# ch340_usb.net
KiCad netlist of a schematic drawn in EAGLE
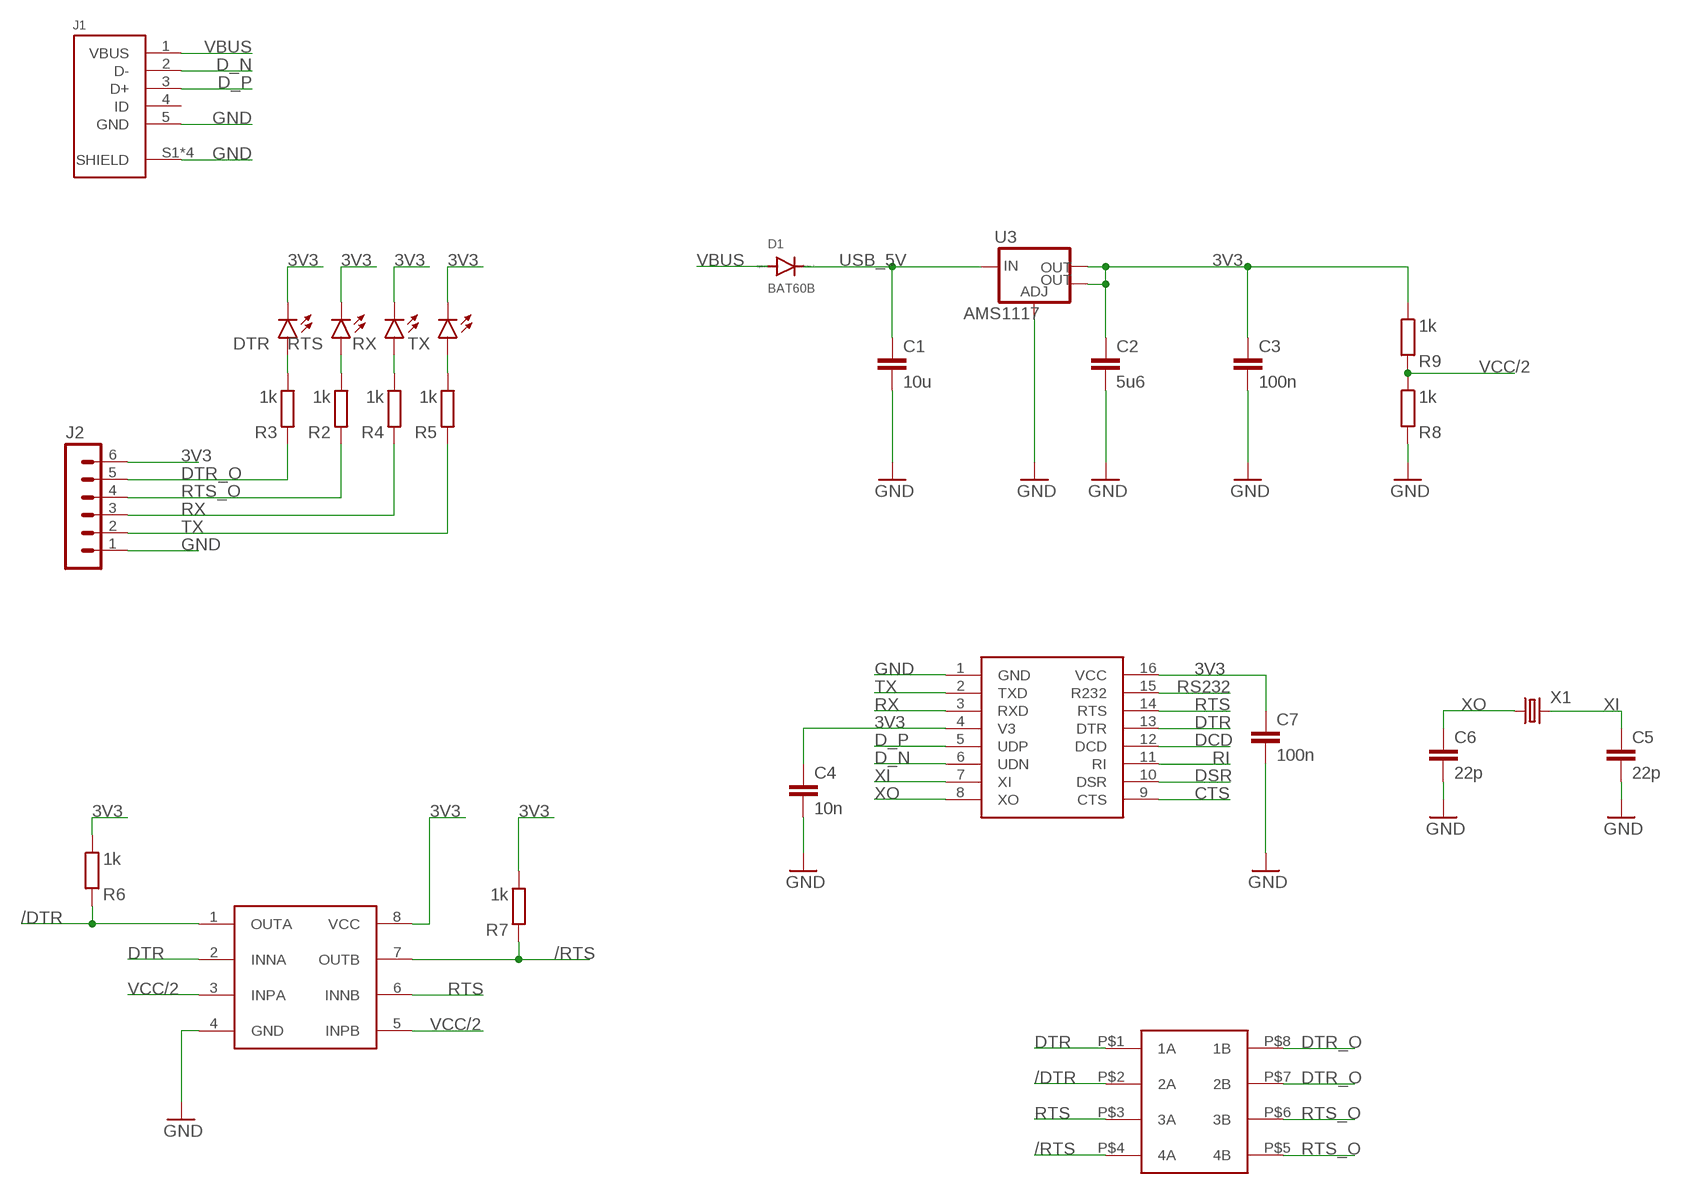
[diagram p0: schematic, sheet 1]

(export (version "E")
  (design (tool "Eeschema 10.0.6"))
  (components
    (comp (ref "C1")
      (value "10u")
      (footprint "eagle-import:C0805K")
      (libsource (lib "eagle-import") (part "C-EUC0805K"))
    )
    (comp (ref "C2")
      (value "5u6")
      (footprint "eagle-import:C0805K")
      (libsource (lib "eagle-import") (part "C-EUC0805K"))
    )
    (comp (ref "C3")
      (value "100n")
      (footprint "eagle-import:C0805K")
      (libsource (lib "eagle-import") (part "C-EUC0805K"))
    )
    (comp (ref "C4")
      (value "10n")
      (footprint "eagle-import:C0805K")
      (libsource (lib "eagle-import") (part "C-EUC0805K"))
    )
    (comp (ref "C5")
      (value "22p")
      (footprint "eagle-import:C0805K")
      (libsource (lib "eagle-import") (part "C-EUC0805K"))
    )
    (comp (ref "C6")
      (value "22p")
      (footprint "eagle-import:C0805K")
      (libsource (lib "eagle-import") (part "C-EUC0805K"))
    )
    (comp (ref "C7")
      (value "100n")
      (footprint "eagle-import:C0805K")
      (libsource (lib "eagle-import") (part "C-EUC0805K"))
    )
    (comp (ref "D1")
      (value "BAT60B")
      (footprint "eagle-import:SOD123")
      (libsource (lib "eagle-import") (part "MBR0520LT"))
    )
    (comp (ref "DTR")
      (value "PWR")
      (footprint "eagle-import:CHIPLED_0805")
      (libsource (lib "eagle-import") (part "LEDCHIPLED_0805"))
    )
    (comp (ref "J1")
      (value "1734035-4")
      (footprint "eagle-import:1734035-4")
      (fields
        (field (name "DIGIKEY_PARTNO") "A121554TR-ND")
        (field (name "MANUFACTURER") "TE Connectivity AMP Connectors")
        (field (name "CREATED_BY") "PCBLayout.com")
      )
      (libsource (lib "eagle-import") (part "1734035-4"))
    )
    (comp (ref "J2")
      (value "MA06-1")
      (footprint "eagle-import:MA06-1")
      (libsource (lib "eagle-import") (part "MA06-1"))
    )
    (comp (ref "R2")
      (value "1k")
      (footprint "eagle-import:R0805")
      (libsource (lib "eagle-import") (part "R-EU_R0805"))
    )
    (comp (ref "R3")
      (value "1k")
      (footprint "eagle-import:R0805")
      (libsource (lib "eagle-import") (part "R-EU_R0805"))
    )
    (comp (ref "R4")
      (value "1k")
      (footprint "eagle-import:R0805")
      (libsource (lib "eagle-import") (part "R-EU_R0805"))
    )
    (comp (ref "R5")
      (value "1k")
      (footprint "eagle-import:R0805")
      (libsource (lib "eagle-import") (part "R-EU_R0805"))
    )
    (comp (ref "R6")
      (value "1k")
      (footprint "eagle-import:R0805")
      (libsource (lib "eagle-import") (part "R-EU_R0805"))
    )
    (comp (ref "R7")
      (value "1k")
      (footprint "eagle-import:R0805")
      (libsource (lib "eagle-import") (part "R-EU_R0805"))
    )
    (comp (ref "R8")
      (value "1k")
      (footprint "eagle-import:R0805")
      (libsource (lib "eagle-import") (part "R-EU_R0805"))
    )
    (comp (ref "R9")
      (value "1k")
      (footprint "eagle-import:R0805")
      (libsource (lib "eagle-import") (part "R-EU_R0805"))
    )
    (comp (ref "RTS")
      (value "PWR")
      (footprint "eagle-import:CHIPLED_0805")
      (libsource (lib "eagle-import") (part "LEDCHIPLED_0805"))
    )
    (comp (ref "RX")
      (value "PWR")
      (footprint "eagle-import:CHIPLED_0805")
      (libsource (lib "eagle-import") (part "LEDCHIPLED_0805"))
    )
    (comp (ref "TX")
      (value "PWR")
      (footprint "eagle-import:CHIPLED_0805")
      (libsource (lib "eagle-import") (part "LEDCHIPLED_0805"))
    )
    (comp (ref "U$1")
      (value "DIPSW4")
      (footprint "eagle-import:4_SMT_2.54")
      (libsource (lib "eagle-import") (part "DIPSW4"))
    )
    (comp (ref "U1")
      (value "HX711")
      (footprint "eagle-import:SOP16")
      (libsource (lib "eagle-import") (part "CH340G"))
    )
    (comp (ref "U2")
      (value "LM393")
      (footprint "eagle-import:SOIC127P600X144-8")
      (libsource (lib "eagle-import") (part "LM393"))
    )
    (comp (ref "U3")
      (value "AMS1117")
      (footprint "eagle-import:SOT223")
      (libsource (lib "eagle-import") (part "V_REG_LM1117SOT223"))
    )
    (comp (ref "X1")
      (value "CSM-7X-DU")
      (footprint "eagle-import:CSM-7X-DU")
      (libsource (lib "eagle-import") (part "CSM-7X-DU"))
    )
  )
  (nets
    (net (code "1") (name "/3V3") (class "Default")
      (node (ref "C2") (pin "1") (pinfunction "1_1") (pintype "passive"))
      (node (ref "C3") (pin "1") (pinfunction "1_1") (pintype "passive"))
      (node (ref "C4") (pin "1") (pinfunction "1_1") (pintype "passive"))
      (node (ref "C7") (pin "1") (pinfunction "1_1") (pintype "passive"))
      (node (ref "DTR") (pin "C") (pinfunction "C_C") (pintype "passive"))
      (node (ref "J2") (pin "6") (pinfunction "6_6") (pintype "passive"))
      (node (ref "R6") (pin "1") (pinfunction "1_1") (pintype "passive"))
      (node (ref "R7") (pin "1") (pinfunction "1_1") (pintype "passive"))
      (node (ref "R9") (pin "1") (pinfunction "1_1") (pintype "passive"))
      (node (ref "RTS") (pin "C") (pinfunction "C_C") (pintype "passive"))
      (node (ref "RX") (pin "C") (pinfunction "C_C") (pintype "passive"))
      (node (ref "TX") (pin "C") (pinfunction "C_C") (pintype "passive"))
      (node (ref "U1") (pin "16") (pinfunction "VCC_16") (pintype "bidirectional"))
      (node (ref "U1") (pin "4") (pinfunction "V3_4") (pintype "bidirectional"))
      (node (ref "U2") (pin "8") (pinfunction "VCC_8") (pintype "bidirectional"))
      (node (ref "U3") (pin "2") (pinfunction "OUT_2") (pintype "output"))
      (node (ref "U3") (pin "4") (pinfunction "OUT_4") (pintype "output"))
    )
    (net (code "2") (name "/CTS") (class "Default")
      (node (ref "U1") (pin "9") (pinfunction "CTS_9") (pintype "bidirectional"))
    )
    (net (code "3") (name "/DCD") (class "Default")
      (node (ref "U1") (pin "12") (pinfunction "DCD_12") (pintype "bidirectional"))
    )
    (net (code "4") (name "/DSR") (class "Default")
      (node (ref "U1") (pin "10") (pinfunction "DSR_10") (pintype "bidirectional"))
    )
    (net (code "5") (name "/DTR") (class "Default")
      (node (ref "U$1") (pin "P$1") (pinfunction "1A_P$1") (pintype "bidirectional"))
      (node (ref "U1") (pin "13") (pinfunction "DTR_13") (pintype "bidirectional"))
      (node (ref "U2") (pin "2") (pinfunction "INNA_2") (pintype "bidirectional"))
    )
    (net (code "6") (name "/DTR_O") (class "Default")
      (node (ref "J2") (pin "5") (pinfunction "5_5") (pintype "passive"))
      (node (ref "R3") (pin "2") (pinfunction "2_2") (pintype "passive"))
      (node (ref "U$1") (pin "P$7") (pinfunction "2B_P$7") (pintype "bidirectional"))
      (node (ref "U$1") (pin "P$8") (pinfunction "1B_P$8") (pintype "bidirectional"))
    )
    (net (code "7") (name "/D_N") (class "Default")
      (node (ref "J1") (pin "2") (pinfunction "D-_2") (pintype "passive"))
      (node (ref "U1") (pin "6") (pinfunction "UDN_6") (pintype "bidirectional"))
    )
    (net (code "8") (name "/D_P") (class "Default")
      (node (ref "J1") (pin "3") (pinfunction "D+_3") (pintype "passive"))
      (node (ref "U1") (pin "5") (pinfunction "UDP_5") (pintype "bidirectional"))
    )
    (net (code "9") (name "/RI") (class "Default")
      (node (ref "U1") (pin "11") (pinfunction "RI_11") (pintype "bidirectional"))
    )
    (net (code "10") (name "/RS232") (class "Default")
      (node (ref "U1") (pin "15") (pinfunction "R232_15") (pintype "bidirectional"))
    )
    (net (code "11") (name "/RTS") (class "Default")
      (node (ref "U$1") (pin "P$3") (pinfunction "3A_P$3") (pintype "bidirectional"))
      (node (ref "U1") (pin "14") (pinfunction "RTS_14") (pintype "bidirectional"))
      (node (ref "U2") (pin "6") (pinfunction "INNB_6") (pintype "bidirectional"))
    )
    (net (code "12") (name "/RTS_O") (class "Default")
      (node (ref "J2") (pin "4") (pinfunction "4_4") (pintype "passive"))
      (node (ref "R2") (pin "2") (pinfunction "2_2") (pintype "passive"))
      (node (ref "U$1") (pin "P$5") (pinfunction "4B_P$5") (pintype "bidirectional"))
      (node (ref "U$1") (pin "P$6") (pinfunction "3B_P$6") (pintype "bidirectional"))
    )
    (net (code "13") (name "/RX") (class "Default")
      (node (ref "J2") (pin "3") (pinfunction "3_3") (pintype "passive"))
      (node (ref "R4") (pin "2") (pinfunction "2_2") (pintype "passive"))
      (node (ref "U1") (pin "3") (pinfunction "RXD_3") (pintype "bidirectional"))
    )
    (net (code "14") (name "/TX") (class "Default")
      (node (ref "J2") (pin "2") (pinfunction "2_2") (pintype "passive"))
      (node (ref "R5") (pin "2") (pinfunction "2_2") (pintype "passive"))
      (node (ref "U1") (pin "2") (pinfunction "TXD_2") (pintype "bidirectional"))
    )
    (net (code "15") (name "/USB_5V") (class "Default")
      (node (ref "C1") (pin "1") (pinfunction "1_1") (pintype "passive"))
      (node (ref "D1") (pin "C") (pinfunction "C_C") (pintype "passive"))
      (node (ref "U3") (pin "3") (pinfunction "IN_3") (pintype "input"))
    )
    (net (code "16") (name "/VBUS") (class "Default")
      (node (ref "D1") (pin "A") (pinfunction "A_A") (pintype "passive"))
      (node (ref "J1") (pin "1") (pinfunction "VBUS_1") (pintype "passive"))
    )
    (net (code "17") (name "/VCC{slash}2") (class "Default")
      (node (ref "R8") (pin "1") (pinfunction "1_1") (pintype "passive"))
      (node (ref "R9") (pin "2") (pinfunction "2_2") (pintype "passive"))
      (node (ref "U2") (pin "3") (pinfunction "INPA_3") (pintype "bidirectional"))
      (node (ref "U2") (pin "5") (pinfunction "INPB_5") (pintype "bidirectional"))
    )
    (net (code "18") (name "/XI") (class "Default")
      (node (ref "C5") (pin "1") (pinfunction "1_1") (pintype "passive"))
      (node (ref "U1") (pin "7") (pinfunction "XI_7") (pintype "bidirectional"))
      (node (ref "X1") (pin "2") (pinfunction "2_2") (pintype "passive"))
    )
    (net (code "19") (name "/XO") (class "Default")
      (node (ref "C6") (pin "1") (pinfunction "1_1") (pintype "passive"))
      (node (ref "U1") (pin "8") (pinfunction "XO_8") (pintype "bidirectional"))
      (node (ref "X1") (pin "1") (pinfunction "1_1") (pintype "passive"))
    )
    (net (code "20") (name "/{slash}DTR") (class "Default")
      (node (ref "R6") (pin "2") (pinfunction "2_2") (pintype "passive"))
      (node (ref "U$1") (pin "P$2") (pinfunction "2A_P$2") (pintype "bidirectional"))
      (node (ref "U2") (pin "1") (pinfunction "OUTA_1") (pintype "bidirectional"))
    )
    (net (code "21") (name "/{slash}RTS") (class "Default")
      (node (ref "R7") (pin "2") (pinfunction "2_2") (pintype "passive"))
      (node (ref "U$1") (pin "P$4") (pinfunction "4A_P$4") (pintype "bidirectional"))
      (node (ref "U2") (pin "7") (pinfunction "OUTB_7") (pintype "bidirectional"))
    )
    (net (code "22") (name "GND") (class "Default")
      (node (ref "C1") (pin "2") (pinfunction "2_2") (pintype "passive"))
      (node (ref "C2") (pin "2") (pinfunction "2_2") (pintype "passive"))
      (node (ref "C3") (pin "2") (pinfunction "2_2") (pintype "passive"))
      (node (ref "C4") (pin "2") (pinfunction "2_2") (pintype "passive"))
      (node (ref "C5") (pin "2") (pinfunction "2_2") (pintype "passive"))
      (node (ref "C6") (pin "2") (pinfunction "2_2") (pintype "passive"))
      (node (ref "C7") (pin "2") (pinfunction "2_2") (pintype "passive"))
      (node (ref "J1") (pin "5") (pinfunction "GND_5") (pintype "passive"))
      (node (ref "J1") (pin "S1") (pinfunction "SHIELD_S1") (pintype "power_in"))
      (node (ref "J1") (pin "S2") (pinfunction "SHIELD_S2") (pintype "power_in"))
      (node (ref "J1") (pin "S3") (pinfunction "SHIELD_S3") (pintype "power_in"))
      (node (ref "J1") (pin "S4") (pinfunction "SHIELD_S4") (pintype "power_in"))
      (node (ref "J2") (pin "1") (pinfunction "1_1") (pintype "passive"))
      (node (ref "R8") (pin "2") (pinfunction "2_2") (pintype "passive"))
      (node (ref "U1") (pin "1") (pinfunction "GND_1") (pintype "bidirectional"))
      (node (ref "U2") (pin "4") (pinfunction "GND_4") (pintype "bidirectional"))
      (node (ref "U3") (pin "1") (pinfunction "ADJ_1") (pintype "input"))
    )
    (net (code "23") (name "Net-(DTR-PadA)") (class "Default")
      (node (ref "DTR") (pin "A") (pinfunction "A_A") (pintype "passive"))
      (node (ref "R3") (pin "1") (pinfunction "1_1") (pintype "passive"))
    )
    (net (code "24") (name "Net-(R2-Pad1)") (class "Default")
      (node (ref "R2") (pin "1") (pinfunction "1_1") (pintype "passive"))
      (node (ref "RTS") (pin "A") (pinfunction "A_A") (pintype "passive"))
    )
    (net (code "25") (name "Net-(R4-Pad1)") (class "Default")
      (node (ref "R4") (pin "1") (pinfunction "1_1") (pintype "passive"))
      (node (ref "RX") (pin "A") (pinfunction "A_A") (pintype "passive"))
    )
    (net (code "26") (name "Net-(R5-Pad1)") (class "Default")
      (node (ref "R5") (pin "1") (pinfunction "1_1") (pintype "passive"))
      (node (ref "TX") (pin "A") (pinfunction "A_A") (pintype "passive"))
    )
    (net (code "27") (name "unconnected-(J1-ID-Pad4)") (class "Default")
      (node (ref "J1") (pin "4") (pinfunction "ID_4") (pintype "passive"))
    )
  )
)
